# ESP32.net
KiCad netlist of a schematic drawn in Altium Designer
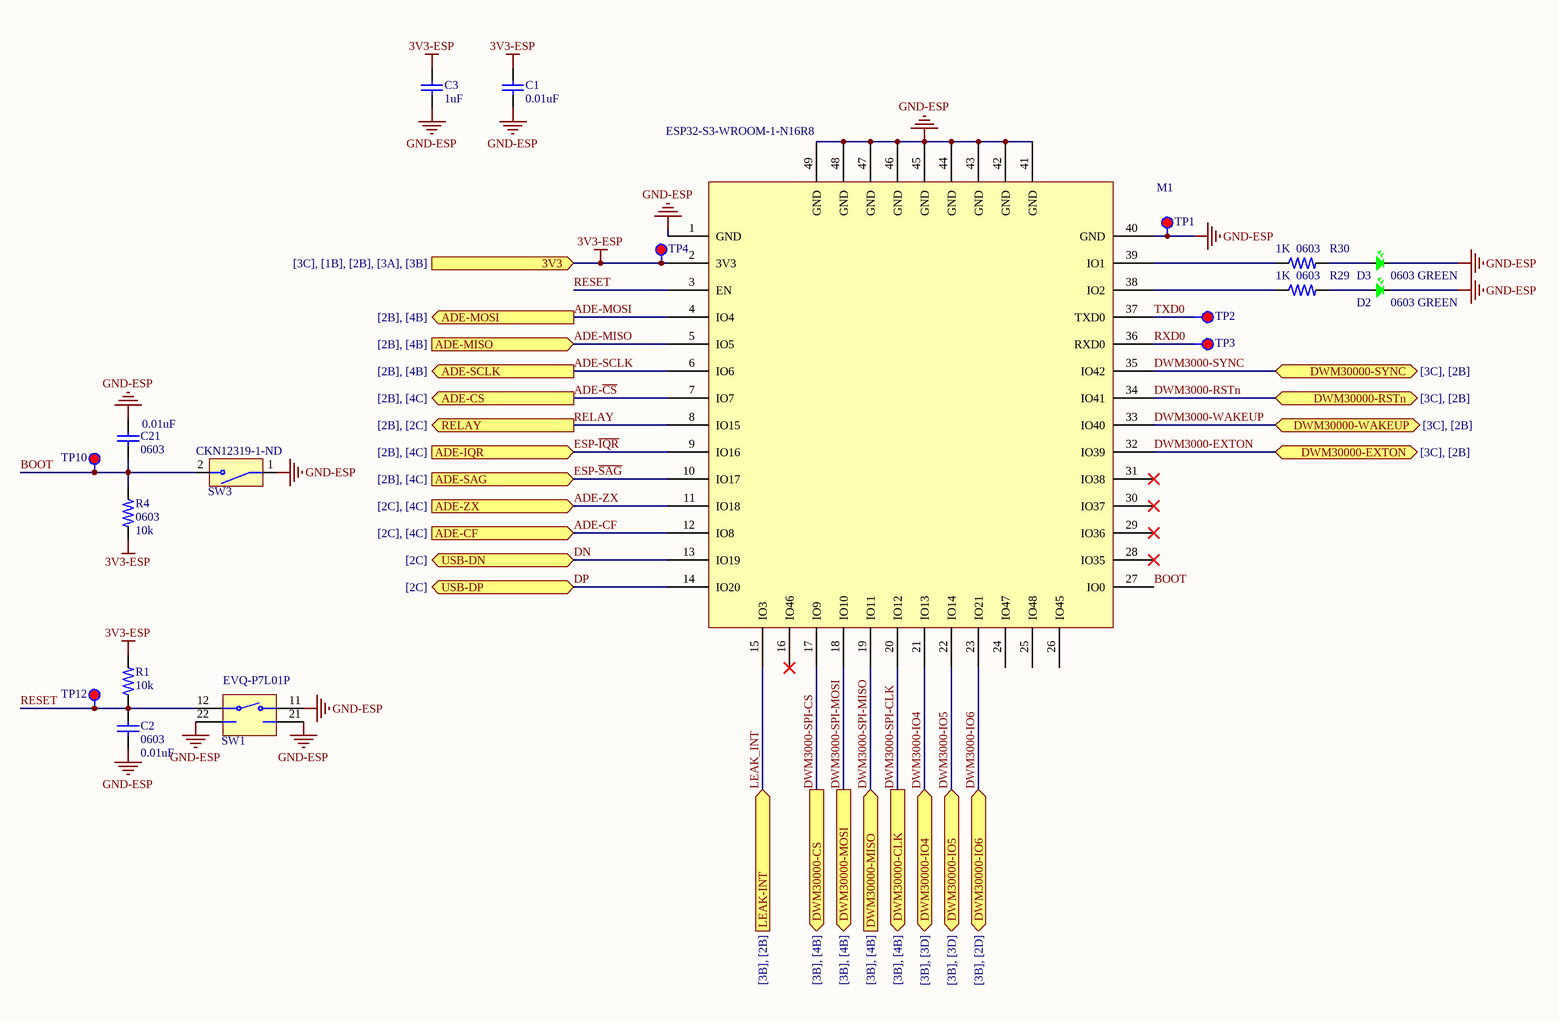
[diagram p0: ESP32.SchDoc]

(export (version "E")
  (design (tool "Eeschema 10.0.6"))
  (components
    (comp (ref "C1")
      (value "0.01uF")
      (footprint "SMD-CAP-0603-YAGEO")
      (description "Multilayer Ceramic Capacitor, 0.1 uF, 10 V, ± 10%, X7R, 0603 [1608 Metric]")
      (fields
        (field (name "MANUFACTURER") "Yageo")
        (field (name "MANUFACTURER PART NUMBER") "CC0603KRX7R6BB104")
        (field (name "DESIGNER") "TVBac")
      )
      (libsource (lib "Capacitors") (part "CAP; 0.1uF; 10V; 0603; SMD; CC0603KRX7R6BB104"))
    )
    (comp (ref "C2")
      (value "0.01uF")
      (footprint "SMD-CAP-0603-YAGEO")
      (description "Multilayer Ceramic Capacitor, 0.01 uF, 16 V, ± 10%, X7R, 0603 [1608 Metric]")
      (fields
        (field (name "MANUFACTURER") "Yageo")
        (field (name "MANUFACTURER PART NUMBER") "CC0603KRX7R7BB103")
        (field (name "PACKAGE") "0603")
        (field (name "DESIGNER") "TVBac")
      )
      (libsource (lib "Capacitors") (part "CAP; 0.01uF; 16V; 0603; SMD; CC0603KRX7R7BB103"))
    )
    (comp (ref "C3")
      (value "1uF")
      (footprint "SMD-CAP-0603-YAGEO")
      (description "0603 1 uF 16 V ±10 % Tolerance X7R SMT Multilayer Ceramic Capacitor")
      (fields
        (field (name "MANUFACTURER") "Yageo")
        (field (name "MANUFACTURER PART NUMBER") "CC0603KRX7R7BB105")
        (field (name "DESIGNER") "TVBac")
      )
      (libsource (lib "Capacitors") (part "CAP; 1uF; 16V; 0603; SMD; CC0603KRX7R7BB105"))
    )
    (comp (ref "C21")
      (value "0.01uF")
      (footprint "SMD-CAP-0603-YAGEO")
      (description "Multilayer Ceramic Capacitor, 0.01 uF, 16 V, ± 10%, X7R, 0603 [1608 Metric]")
      (fields
        (field (name "MANUFACTURER") "Yageo")
        (field (name "MANUFACTURER PART NUMBER") "CC0603KRX7R7BB103")
        (field (name "PACKAGE") "0603")
        (field (name "DESIGNER") "TVBac")
      )
      (libsource (lib "Capacitors") (part "CAP; 0.01uF; 16V; 0603; SMD; CC0603KRX7R7BB103"))
    )
    (comp (ref "D2")
      (value "0603 GREEN")
      (footprint "LED0603_GREEN")
      (fields
        (field (name "MANUFACTURER") "Amicc")
        (field (name "MANUFACTURE PART NUMBER") "A-SP192DGHC-C01-4T")
      )
      (libsource (lib "LED") (part "L0603_GREEN"))
    )
    (comp (ref "D3")
      (value "0603 GREEN")
      (footprint "LED0603_GREEN")
      (fields
        (field (name "MANUFACTURER") "Amicc")
        (field (name "MANUFACTURE PART NUMBER") "A-SP192DGHC-C01-4T")
      )
      (libsource (lib "LED") (part "L0603_GREEN"))
    )
    (comp (ref "M1")
      (value "Bluetooth, WiFi 802.11b/g/n, Bluetooth v4.2 +EDR Transceiver Module 2.4GHz ~ 2.5GHz PCB Trace Surface Mount")
      (footprint "MODULE-ESP32-S3-WROOM-1-N16R8")
      (description "SMD mod, ESP32-S3R8 with 3.3V, 8MB Octal PSRAM die insid, 6MBQuad SPI flash, pcb ant")
      (fields
        (field (name "MANUFACTURER") "Espressif Systems")
        (field (name "MANUFACTURER PART NUMBER") "ESP32-S3-WROOM-1-N16R8")
        (field (name "DESIGNER") "TVBac")
      )
      (libsource (lib "Modules") (part "ESP32-S3-WROOM-1-N16R8; SMD;"))
    )
    (comp (ref "R1")
      (value "10k")
      (footprint "SMD-RES-0603-SEI")
      (description "SMD Chip Resistor, 10 kOhm, ± 1%, 250 mW, 0603 [1608 Metric], Thick Film, Anti-Surge")
      (fields
        (field (name "MANUFACTURER") "Rohm")
        (field (name "MANUFACTURER PART NUMBER") "ESR03EZPF1002")
        (field (name "DESIGNER") "TVBac")
      )
      (libsource (lib "Smartsocket") (part "RES; 10K; 0603; SMD; ESR03EZPF1002"))
    )
    (comp (ref "R4")
      (value "10k")
      (footprint "SMD-RES-0603-SEI")
      (description "SMD Chip Resistor, 10 kOhm, ± 1%, 250 mW, 0603 [1608 Metric], Thick Film, Anti-Surge")
      (fields
        (field (name "MANUFACTURER") "Rohm")
        (field (name "MANUFACTURER PART NUMBER") "ESR03EZPF1002")
        (field (name "PACKAGE") "0603")
        (field (name "DESIGNER") "TVBac")
      )
      (libsource (lib "Resistors") (part "RES; 10K; 0603; SMD; ESR03EZPF1002"))
    )
    (comp (ref "R29")
      (value "1K")
      (footprint "SMD-RES-0603-SEI")
      (description "SMD Chip Resistor, 1 kOhm, ± 1%, 250 mW, 0603 [1608 Metric], Thick Film, Anti-Surge")
      (fields
        (field (name "MANUFACTURER") "Rohm")
        (field (name "MANUFACTURER PART NUMBER") "ESR03EZPF1001")
        (field (name "PACKAGE") "0603")
        (field (name "DESIGNER") "TVBac")
      )
      (libsource (lib "Resistors") (part "RES; 1K; 0603; SMD; ESR03EZPF1001"))
    )
    (comp (ref "R30")
      (value "1K")
      (footprint "SMD-RES-0603-SEI")
      (description "SMD Chip Resistor, 1 kOhm, ± 1%, 250 mW, 0603 [1608 Metric], Thick Film, Anti-Surge")
      (fields
        (field (name "MANUFACTURER") "Rohm")
        (field (name "MANUFACTURER PART NUMBER") "ESR03EZPF1001")
        (field (name "PACKAGE") "0603")
        (field (name "DESIGNER") "TVBac")
      )
      (libsource (lib "Resistors") (part "RES; 1K; 0603; SMD; ESR03EZPF1001"))
    )
    (comp (ref "SW1")
      (value "https://www.digikey.com/en/products/detail/panasonic-electronic-components/EVQ-P7L01P/4429453")
      (footprint "SW-HxLxW-1.1x3.5x2.9-PEC")
      (description "Tactile Switch SPST-NO Side Actuated Surface Mount, Right Angle")
      (fields
        (field (name "MP") "EVQ-P7L01P")
        (field (name "MF") "Panasonic Electronic Components")
        (field (name "DIGI-KEY_PART_NUMBER") "P16769TR-ND")
      )
      (libsource (lib "Button") (part "BUT; SW; SMD; EVQ-P7L01P"))
    )
    (comp (ref "SW3")
      (value "Tactile Switch SPST-NO Top Actuated Surface Mount")
      (footprint "SW-HxLxW-5.0x6.0x3.5-C&K")
      (description "Switch Tactile N.O. SPST Rectangular Button J-Bend 0.05A 12VDC 1.77N SMD T/R")
      (fields
        (field (name "SUPPLIER PART NUMBER") "CKN12319-1-ND")
        (field (name "MANUFACTURER") "ITT C&K")
        (field (name "MANUFACTURER PART NUMBER") "PTS636SM50JSMTRLFS")
      )
      (libsource (lib "Button") (part "BUT; SW; SMD; PTS636SM50JSMTRLFS"))
    )
    (comp (ref "TP1")
      (value "Test Point")
      (footprint "TEST_POINT")
      (libsource (lib "Socket") (part "TEST_POINT"))
    )
    (comp (ref "TP2")
      (value "Test Point")
      (footprint "TEST_POINT")
      (libsource (lib "Socket") (part "TEST_POINT"))
    )
    (comp (ref "TP3")
      (value "Test Point")
      (footprint "TEST_POINT")
      (libsource (lib "Socket") (part "TEST_POINT"))
    )
    (comp (ref "TP4")
      (value "Test Point")
      (footprint "TEST_POINT")
      (libsource (lib "Socket") (part "TEST_POINT"))
    )
    (comp (ref "TP10")
      (value "Test Point")
      (footprint "TEST_POINT")
      (libsource (lib "Socket") (part "TEST_POINT"))
    )
    (comp (ref "TP12")
      (value "Test Point")
      (footprint "TEST_POINT")
      (libsource (lib "Socket") (part "TEST_POINT"))
    )
  )
  (nets
    (net (code "1") (name "/ADE-CF") (class "Default")
      (node (ref "M1") (pin "12") (pinfunction "IO8_12") (pintype "passive"))
    )
    (net (code "2") (name "/ADE-MISO") (class "Default")
      (node (ref "M1") (pin "5") (pinfunction "IO5_5") (pintype "passive"))
    )
    (net (code "3") (name "/ADE-MOSI") (class "Default")
      (node (ref "M1") (pin "4") (pinfunction "IO4_4") (pintype "passive"))
    )
    (net (code "4") (name "/ADE-SCLK") (class "Default")
      (node (ref "M1") (pin "6") (pinfunction "IO6_6") (pintype "passive"))
    )
    (net (code "5") (name "/ADE-ZX") (class "Default")
      (node (ref "M1") (pin "11") (pinfunction "IO18_11") (pintype "passive"))
    )
    (net (code "6") (name "/ADE-~{CS}") (class "Default")
      (node (ref "M1") (pin "7") (pinfunction "IO7_7") (pintype "passive"))
    )
    (net (code "7") (name "/BOOT") (class "Default")
      (node (ref "C21") (pin "2") (pinfunction "2_2") (pintype "passive"))
      (node (ref "M1") (pin "27") (pinfunction "IO0_27") (pintype "passive"))
      (node (ref "R4") (pin "1") (pinfunction "1_1") (pintype "passive"))
      (node (ref "SW3") (pin "2") (pinfunction "NO_2") (pintype "passive"))
      (node (ref "TP10") (pin "1") (pinfunction "1_1") (pintype "passive"))
    )
    (net (code "8") (name "/DN") (class "Default")
      (node (ref "M1") (pin "13") (pinfunction "IO19_13") (pintype "passive"))
    )
    (net (code "9") (name "/DP") (class "Default")
      (node (ref "M1") (pin "14") (pinfunction "IO20_14") (pintype "passive"))
    )
    (net (code "10") (name "/DWM3000-EXTON") (class "Default")
      (node (ref "M1") (pin "32") (pinfunction "IO39_32") (pintype "passive"))
    )
    (net (code "11") (name "/DWM3000-IO4") (class "Default")
      (node (ref "M1") (pin "21") (pinfunction "IO13_21") (pintype "passive"))
    )
    (net (code "12") (name "/DWM3000-IO5") (class "Default")
      (node (ref "M1") (pin "22") (pinfunction "IO14_22") (pintype "passive"))
    )
    (net (code "13") (name "/DWM3000-IO6") (class "Default")
      (node (ref "M1") (pin "23") (pinfunction "IO21_23") (pintype "passive"))
    )
    (net (code "14") (name "/DWM3000-RSTn") (class "Default")
      (node (ref "M1") (pin "34") (pinfunction "IO41_34") (pintype "passive"))
    )
    (net (code "15") (name "/DWM3000-SPI-CLK") (class "Default")
      (node (ref "M1") (pin "20") (pinfunction "IO12_20") (pintype "passive"))
    )
    (net (code "16") (name "/DWM3000-SPI-CS") (class "Default")
      (node (ref "M1") (pin "17") (pinfunction "IO9_17") (pintype "passive"))
    )
    (net (code "17") (name "/DWM3000-SPI-MISO") (class "Default")
      (node (ref "M1") (pin "19") (pinfunction "IO11_19") (pintype "passive"))
    )
    (net (code "18") (name "/DWM3000-SPI-MOSI") (class "Default")
      (node (ref "M1") (pin "18") (pinfunction "IO10_18") (pintype "passive"))
    )
    (net (code "19") (name "/DWM3000-SYNC") (class "Default")
      (node (ref "M1") (pin "35") (pinfunction "IO42_35") (pintype "passive"))
    )
    (net (code "20") (name "/DWM3000-WAKEUP") (class "Default")
      (node (ref "M1") (pin "33") (pinfunction "IO40_33") (pintype "passive"))
    )
    (net (code "21") (name "/ESP-~{IQR}") (class "Default")
      (node (ref "M1") (pin "9") (pinfunction "IO16_9") (pintype "passive"))
    )
    (net (code "22") (name "/ESP-~{SAG}") (class "Default")
      (node (ref "M1") (pin "10") (pinfunction "IO17_10") (pintype "passive"))
    )
    (net (code "23") (name "/LEAK_INT") (class "Default")
      (node (ref "M1") (pin "15") (pinfunction "IO3_15") (pintype "passive"))
    )
    (net (code "24") (name "/RELAY") (class "Default")
      (node (ref "M1") (pin "8") (pinfunction "IO15_8") (pintype "passive"))
    )
    (net (code "25") (name "/RESET") (class "Default")
      (node (ref "C2") (pin "2") (pinfunction "2_2") (pintype "passive"))
      (node (ref "M1") (pin "3") (pinfunction "EN_3") (pintype "passive"))
      (node (ref "R1") (pin "1") (pinfunction "1_1") (pintype "passive"))
      (node (ref "SW1") (pin "12") (pinfunction "2_12") (pintype "passive"))
      (node (ref "TP12") (pin "1") (pinfunction "1_1") (pintype "passive"))
    )
    (net (code "26") (name "/RXD0") (class "Default")
      (node (ref "M1") (pin "36") (pinfunction "RXD0_36") (pintype "passive"))
      (node (ref "TP3") (pin "1") (pinfunction "1_1") (pintype "passive"))
    )
    (net (code "27") (name "/TXD0") (class "Default")
      (node (ref "M1") (pin "37") (pinfunction "TXD0_37") (pintype "passive"))
      (node (ref "TP2") (pin "1") (pinfunction "1_1") (pintype "passive"))
    )
    (net (code "28") (name "3V3-ESP") (class "Default")
      (node (ref "C1") (pin "2") (pinfunction "2_2") (pintype "passive"))
      (node (ref "C3") (pin "2") (pinfunction "2_2") (pintype "passive"))
      (node (ref "M1") (pin "2") (pinfunction "3V3_2") (pintype "passive"))
      (node (ref "R1") (pin "2") (pinfunction "2_2") (pintype "passive"))
      (node (ref "R4") (pin "2") (pinfunction "2_2") (pintype "passive"))
      (node (ref "TP4") (pin "1") (pinfunction "1_1") (pintype "passive"))
    )
    (net (code "29") (name "GND-ESP") (class "Default")
      (node (ref "C1") (pin "1") (pinfunction "1_1") (pintype "passive"))
      (node (ref "C2") (pin "1") (pinfunction "1_1") (pintype "passive"))
      (node (ref "C21") (pin "1") (pinfunction "1_1") (pintype "passive"))
      (node (ref "C3") (pin "1") (pinfunction "1_1") (pintype "passive"))
      (node (ref "D2") (pin "2") (pinfunction "2_2") (pintype "passive"))
      (node (ref "D3") (pin "2") (pinfunction "2_2") (pintype "passive"))
      (node (ref "M1") (pin "1") (pinfunction "GND_1") (pintype "passive"))
      (node (ref "M1") (pin "40") (pinfunction "GND_40") (pintype "passive"))
      (node (ref "M1") (pin "41") (pinfunction "GND_41") (pintype "passive"))
      (node (ref "M1") (pin "42") (pinfunction "GND_42") (pintype "passive"))
      (node (ref "M1") (pin "43") (pinfunction "GND_43") (pintype "passive"))
      (node (ref "M1") (pin "44") (pinfunction "GND_44") (pintype "passive"))
      (node (ref "M1") (pin "45") (pinfunction "GND_45") (pintype "passive"))
      (node (ref "M1") (pin "46") (pinfunction "GND_46") (pintype "passive"))
      (node (ref "M1") (pin "47") (pinfunction "GND_47") (pintype "passive"))
      (node (ref "M1") (pin "48") (pinfunction "GND_48") (pintype "passive"))
      (node (ref "M1") (pin "49") (pinfunction "GND_49") (pintype "passive"))
      (node (ref "SW1") (pin "11") (pinfunction "1_11") (pintype "passive"))
      (node (ref "SW1") (pin "21") (pinfunction "1_21") (pintype "passive"))
      (node (ref "SW1") (pin "22") (pinfunction "2_22") (pintype "passive"))
      (node (ref "SW3") (pin "1") (pinfunction "COM_1") (pintype "passive"))
      (node (ref "TP1") (pin "1") (pinfunction "1_1") (pintype "passive"))
    )
    (net (code "30") (name "Net-(D2-Pad1)") (class "Default")
      (node (ref "D2") (pin "1") (pinfunction "1_1") (pintype "passive"))
      (node (ref "R29") (pin "2") (pinfunction "2_2") (pintype "passive"))
    )
    (net (code "31") (name "Net-(D3-Pad1)") (class "Default")
      (node (ref "D3") (pin "1") (pinfunction "1_1") (pintype "passive"))
      (node (ref "R30") (pin "2") (pinfunction "2_2") (pintype "passive"))
    )
    (net (code "32") (name "Net-(M1-IO1)") (class "Default")
      (node (ref "M1") (pin "39") (pinfunction "IO1_39") (pintype "passive"))
      (node (ref "R30") (pin "1") (pinfunction "1_1") (pintype "passive"))
    )
    (net (code "33") (name "Net-(M1-IO2)") (class "Default")
      (node (ref "M1") (pin "38") (pinfunction "IO2_38") (pintype "passive"))
      (node (ref "R29") (pin "1") (pinfunction "1_1") (pintype "passive"))
    )
    (net (code "34") (name "unconnected-(M1-IO35-Pad28)") (class "Default")
      (node (ref "M1") (pin "28") (pinfunction "IO35_28") (pintype "passive+no_connect"))
    )
    (net (code "35") (name "unconnected-(M1-IO36-Pad29)") (class "Default")
      (node (ref "M1") (pin "29") (pinfunction "IO36_29") (pintype "passive+no_connect"))
    )
    (net (code "36") (name "unconnected-(M1-IO37-Pad30)") (class "Default")
      (node (ref "M1") (pin "30") (pinfunction "IO37_30") (pintype "passive+no_connect"))
    )
    (net (code "37") (name "unconnected-(M1-IO38-Pad31)") (class "Default")
      (node (ref "M1") (pin "31") (pinfunction "IO38_31") (pintype "passive+no_connect"))
    )
    (net (code "38") (name "unconnected-(M1-IO45-Pad26)") (class "Default")
      (node (ref "M1") (pin "26") (pinfunction "IO45_26") (pintype "passive"))
    )
    (net (code "39") (name "unconnected-(M1-IO46-Pad16)") (class "Default")
      (node (ref "M1") (pin "16") (pinfunction "IO46_16") (pintype "passive+no_connect"))
    )
    (net (code "40") (name "unconnected-(M1-IO47-Pad24)") (class "Default")
      (node (ref "M1") (pin "24") (pinfunction "IO47_24") (pintype "passive"))
    )
    (net (code "41") (name "unconnected-(M1-IO48-Pad25)") (class "Default")
      (node (ref "M1") (pin "25") (pinfunction "IO48_25") (pintype "passive"))
    )
  )
)
